# 20190105_ORIGAMI_V1-V-2.net
KiCad netlist of a schematic drawn in EAGLE
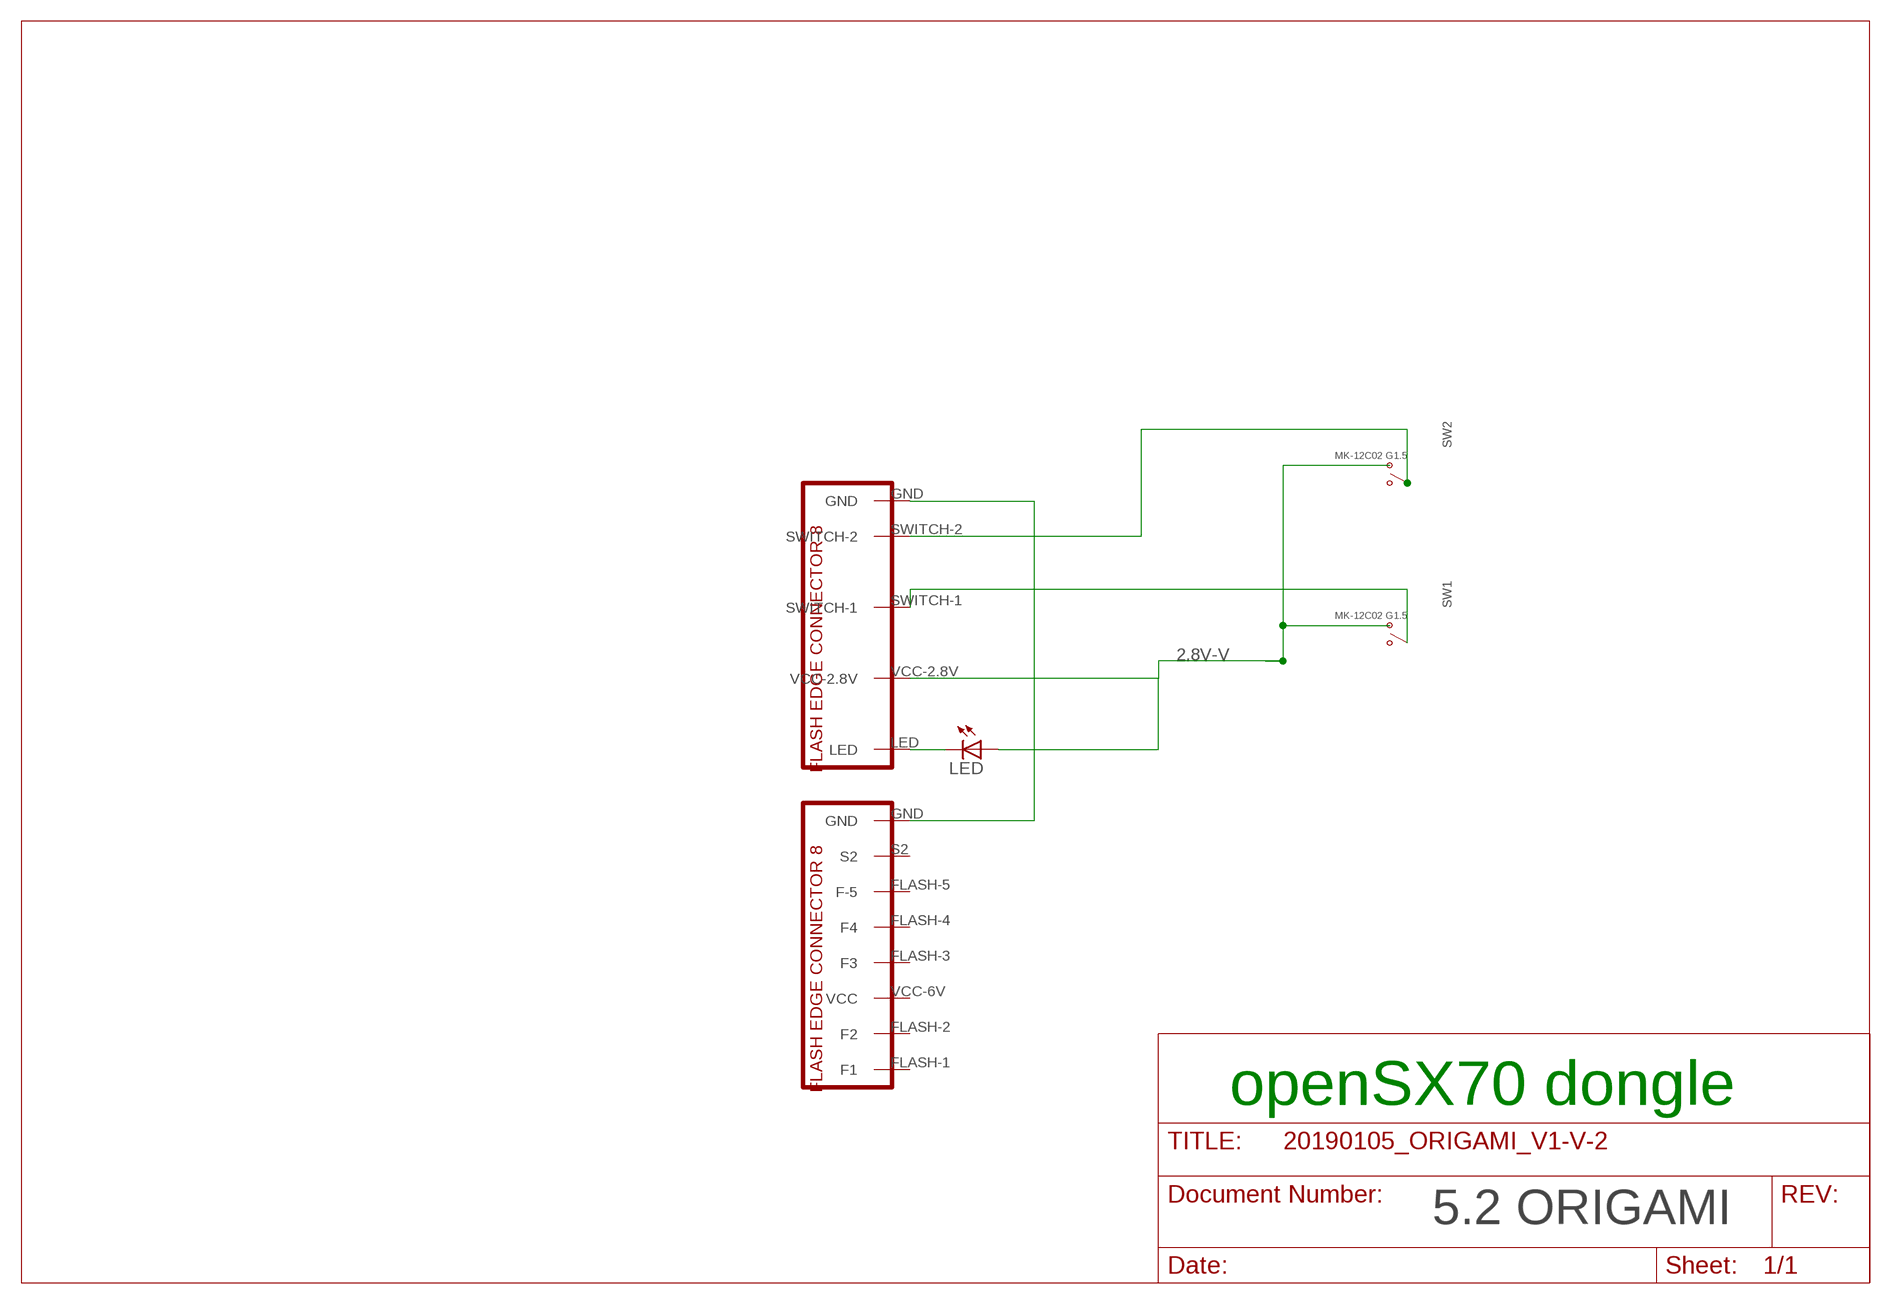
[diagram p0: schematic, sheet 1]

(export (version "E")
  (design (tool "Eeschema 10.0.6"))
  (components
    (comp (ref "LED")
      (value "LEDCHIP-LED0805")
      (footprint "eagle-import:CHIP-LED0805")
      (libsource (lib "eagle-import") (part "LEDCHIP-LED0805"))
    )
    (comp (ref "SW1")
      (value "MK-12C02 G1.5")
      (footprint "eagle-import:SSSS810701")
      (fields (field (name "MF") "ALPS") (field (name "MP") "SSSS810701"))
      (libsource (lib "eagle-import") (part "SSSS810701"))
    )
    (comp (ref "SW2")
      (value "MK-12C02 G1.5")
      (footprint "eagle-import:SSSS810701")
      (fields (field (name "MF") "ALPS") (field (name "MP") "SSSS810701"))
      (libsource (lib "eagle-import") (part "SSSS810701"))
    )
    (comp (ref "U$1")
      (value "FLASH-BRIDGE-SW1-SW2-LED-SMALL")
      (footprint "eagle-import:FLASH-8-BRIDGE-SW1-SW2-LED-SMALL")
      (libsource (lib "eagle-import") (part "FLASH-BRIDGE-SW1-SW2-LED-SMALL"))
    )
    (comp (ref "U$2")
      (value "SX70-FLASH-EDGE8-MALE-LONG")
      (footprint "eagle-import:SX70-FLASH-EDGE8-2")
      (libsource (lib "eagle-import") (part "SX70-FLASH-EDGE8-MALE-LONG"))
    )
  )
  (nets
    (net (code "1") (name "/2.8V-V") (class "Default")
      (node (ref "LED") (pin "A") (pinfunction "A_A") (pintype "passive"))
      (node (ref "SW1") (pin "1") (pinfunction "B_1") (pintype "bidirectional"))
      (node (ref "SW2") (pin "1") (pinfunction "B_1") (pintype "bidirectional"))
      (node (ref "U$1") (pin "VCC-2.8V") (pinfunction "VCC-2.8V_VCC-2.8V") (pintype "bidirectional"))
    )
    (net (code "2") (name "Net-(LED-PadC)") (class "Default")
      (node (ref "LED") (pin "C") (pinfunction "C_C") (pintype "passive"))
      (node (ref "U$1") (pin "LED") (pinfunction "LED_LED") (pintype "bidirectional"))
    )
    (net (code "3") (name "Net-(SW1-COM)") (class "Default")
      (node (ref "SW1") (pin "2") (pinfunction "COM_2") (pintype "bidirectional"))
      (node (ref "U$1") (pin "SWITCH-1") (pinfunction "SWITCH-1_SWITCH-1") (pintype "bidirectional"))
    )
    (net (code "4") (name "Net-(SW2-COM)") (class "Default")
      (node (ref "SW2") (pin "2") (pinfunction "COM_2") (pintype "bidirectional"))
      (node (ref "U$1") (pin "SWITCH-2") (pinfunction "SWITCH-2_SWITCH-2") (pintype "bidirectional"))
    )
    (net (code "5") (name "Net-(U$1-PadGND)") (class "Default")
      (node (ref "U$1") (pin "GND") (pinfunction "GND_GND") (pintype "bidirectional"))
      (node (ref "U$2") (pin "GND") (pinfunction "GND_GND") (pintype "bidirectional"))
    )
    (net (code "6") (name "unconnected-(SW1-A-Pad3)") (class "Default")
      (node (ref "SW1") (pin "3") (pinfunction "A_3") (pintype "bidirectional"))
    )
    (net (code "7") (name "unconnected-(SW2-A-Pad3)") (class "Default")
      (node (ref "SW2") (pin "3") (pinfunction "A_3") (pintype "bidirectional"))
    )
    (net (code "8") (name "unconnected-(U$2-F-5-PadFLASH-5)") (class "Default")
      (node (ref "U$2") (pin "FLASH-5") (pinfunction "F-5_FLASH-5") (pintype "bidirectional"))
    )
    (net (code "9") (name "unconnected-(U$2-F1-PadFLASH-1)") (class "Default")
      (node (ref "U$2") (pin "FLASH-1") (pinfunction "F1_FLASH-1") (pintype "bidirectional"))
    )
    (net (code "10") (name "unconnected-(U$2-F2-PadFLASH-2)") (class "Default")
      (node (ref "U$2") (pin "FLASH-2") (pinfunction "F2_FLASH-2") (pintype "bidirectional"))
    )
    (net (code "11") (name "unconnected-(U$2-F3-PadFLASH-3)") (class "Default")
      (node (ref "U$2") (pin "FLASH-3") (pinfunction "F3_FLASH-3") (pintype "bidirectional"))
    )
    (net (code "12") (name "unconnected-(U$2-F4-PadFLASH-4)") (class "Default")
      (node (ref "U$2") (pin "FLASH-4") (pinfunction "F4_FLASH-4") (pintype "bidirectional"))
    )
    (net (code "13") (name "unconnected-(U$2-PadS2)") (class "Default")
      (node (ref "U$2") (pin "S2") (pinfunction "S2_S2") (pintype "bidirectional"))
    )
    (net (code "14") (name "unconnected-(U$2-VCC-PadVCC-6V)") (class "Default")
      (node (ref "U$2") (pin "VCC-6V") (pinfunction "VCC_VCC-6V") (pintype "bidirectional"))
    )
  )
)
